# FoodTag_ADC_Schematic.net
KiCad netlist of a schematic drawn in EasyEDA
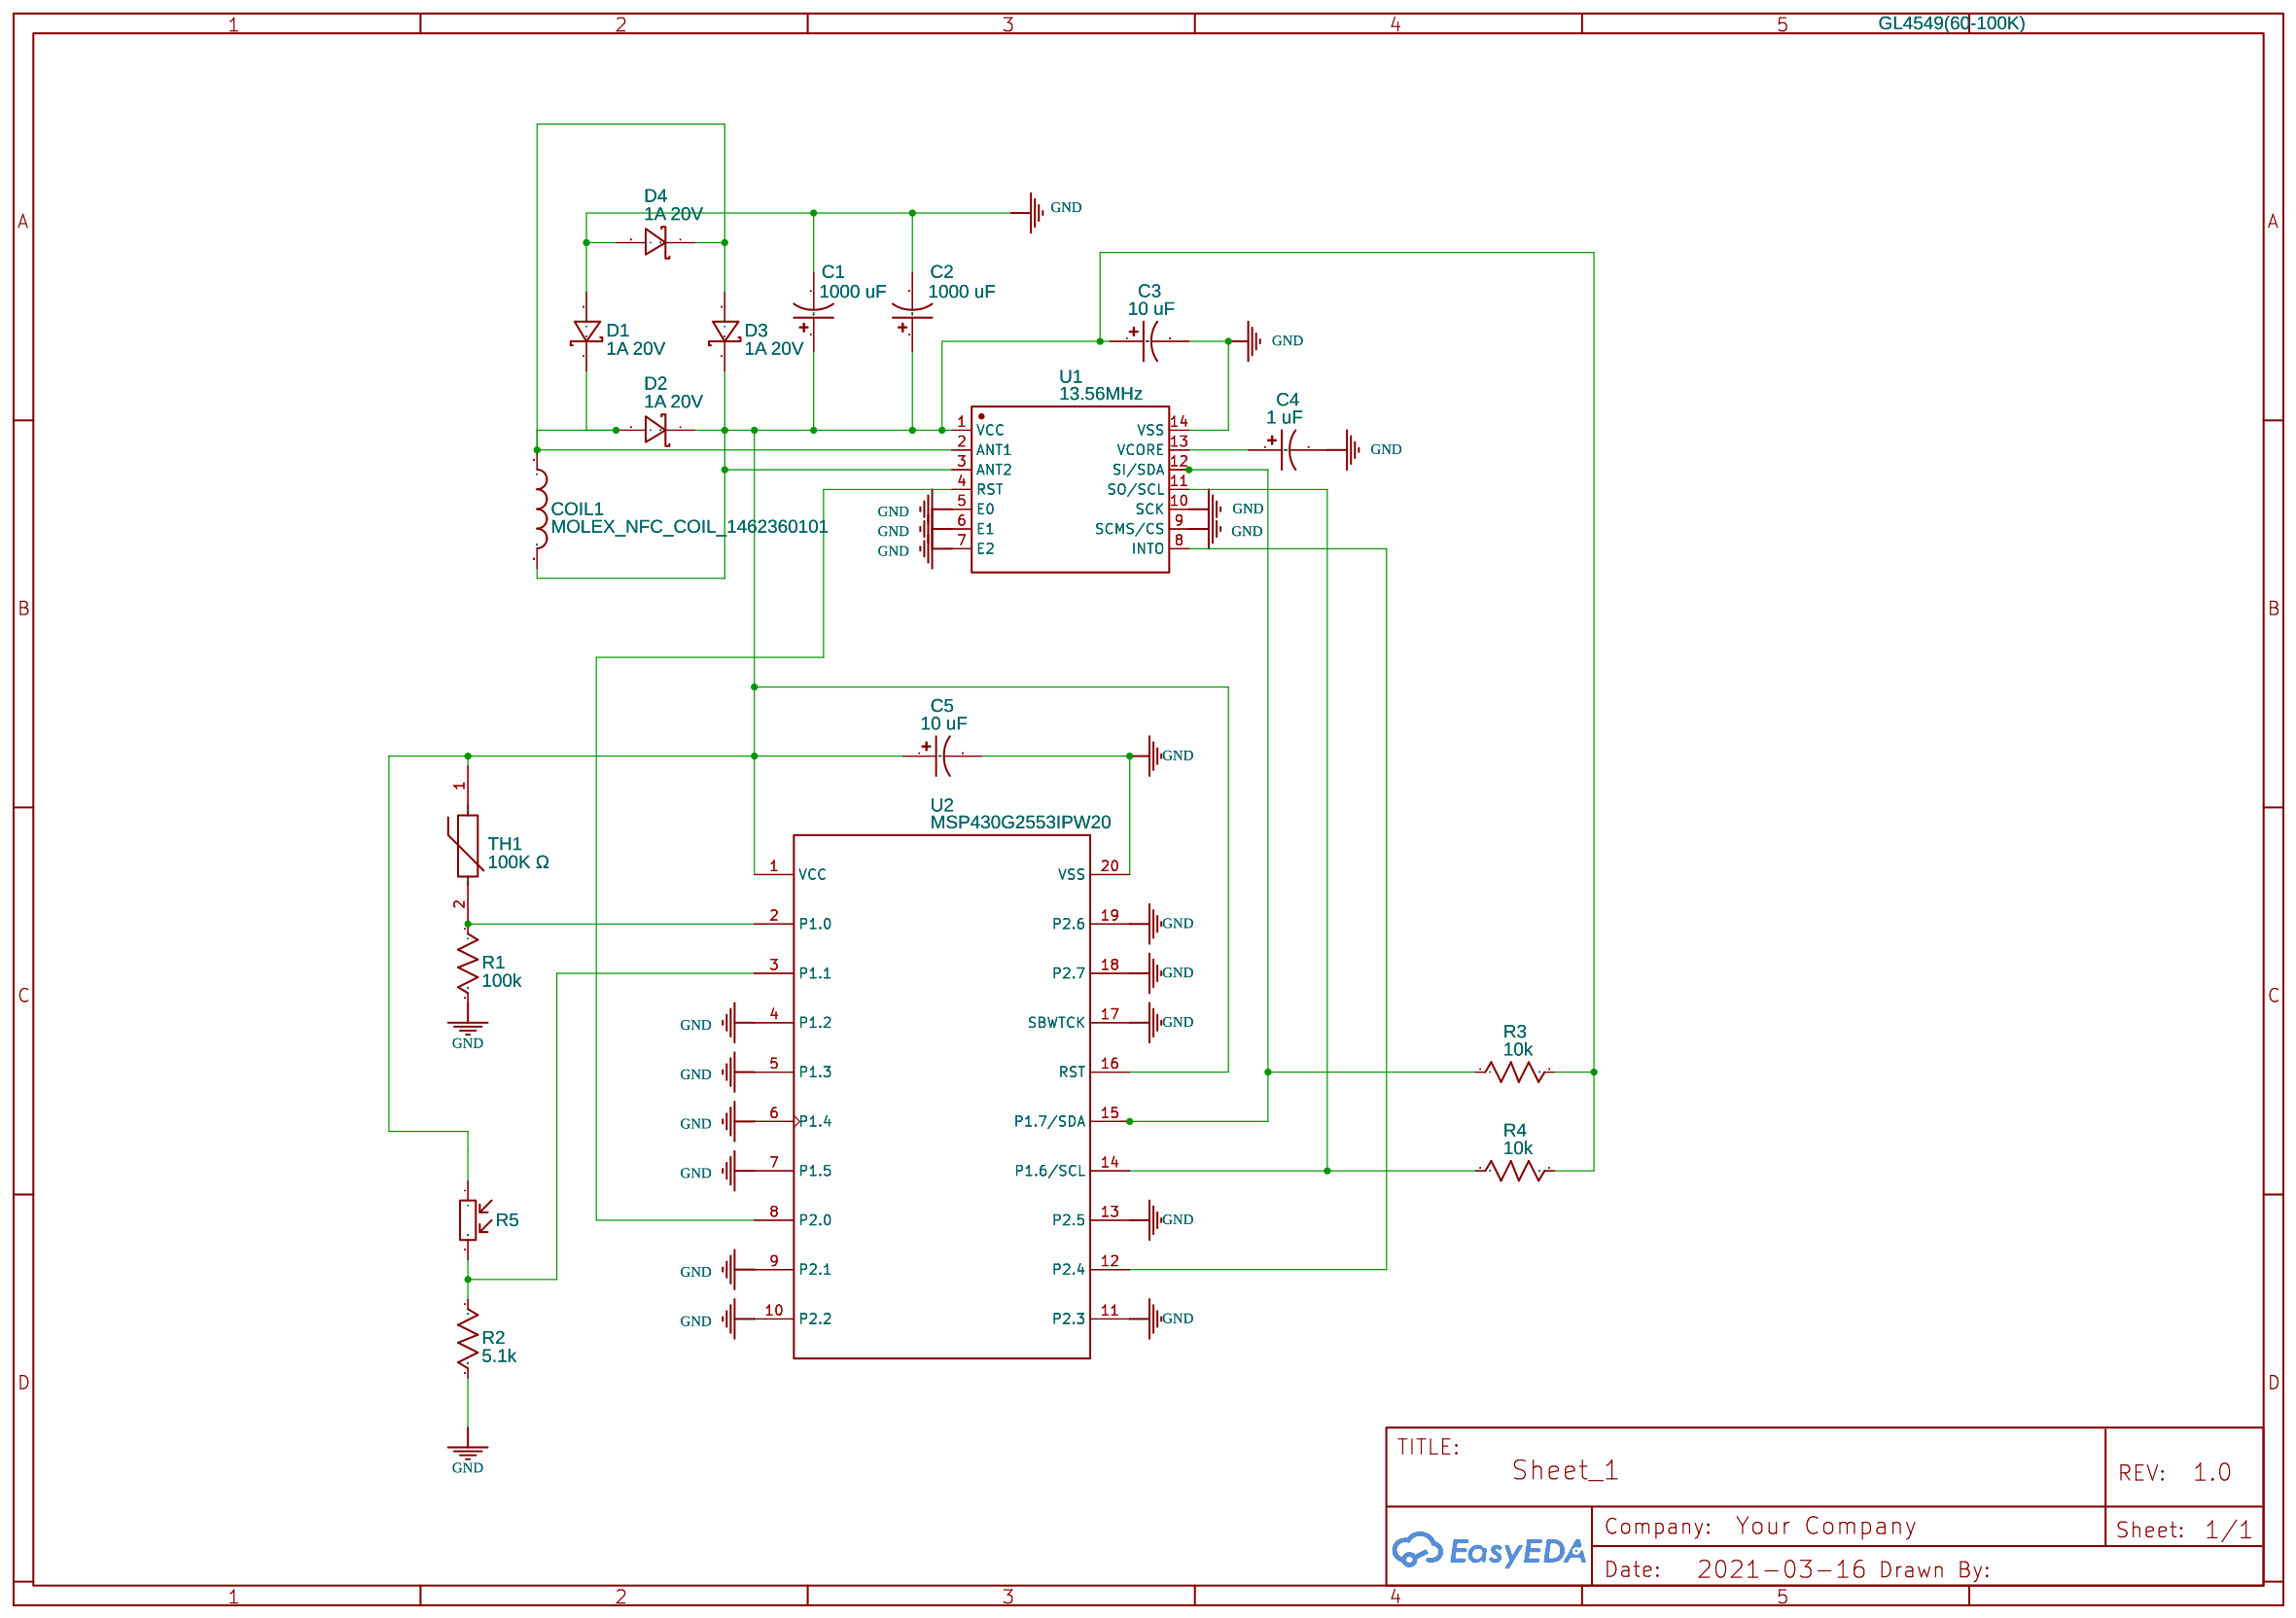
[diagram p0: schematic sheet]

(export (version "E")
  (design (tool "Eeschema 10.0.6"))
  (components
    (comp (ref "C1") (value "1000 uF") (libsource (lib "") (part "C_Tan_SMD_A_US")))
    (comp (ref "C2") (value "1000 uF") (libsource (lib "") (part "C_Tan_SMD_A_US")))
    (comp (ref "C3") (value "10 uF") (libsource (lib "") (part "C_Tan_SMD_A_US_1")))
    (comp (ref "C4") (value "1 uF") (libsource (lib "") (part "C_Tan_SMD_A_US_1")))
    (comp (ref "C5") (value "10 uF") (libsource (lib "") (part "C_Tan_SMD_A_US_1")))
    (comp (ref "COIL1")
      (value "MOLEX_NFC_COIL_1462360101")
      (libsource (lib "") (part "MOLEX_NFC_COIL_1462360101"))
    )
    (comp (ref "D1")
      (value "1A 20V")
      (fields
        (field (name "BOM_Manufacturer Part") "PMEG2010EA,115")
        (field (name "BOM_Supplier Part") "C193668")
      )
      (libsource (lib "") (part "PMEG2010EA,115_1"))
    )
    (comp (ref "D2")
      (value "1A 20V")
      (fields
        (field (name "BOM_Manufacturer Part") "PMEG2010EA,115")
        (field (name "BOM_Supplier Part") "C193668")
      )
      (libsource (lib "") (part "PMEG2010EA,115"))
    )
    (comp (ref "D3")
      (value "1A 20V")
      (fields
        (field (name "BOM_Manufacturer Part") "PMEG2010EA,115")
        (field (name "BOM_Supplier Part") "C193668")
      )
      (libsource (lib "") (part "PMEG2010EA,115_1"))
    )
    (comp (ref "D4")
      (value "1A 20V")
      (fields
        (field (name "BOM_Manufacturer Part") "PMEG2010EA,115")
        (field (name "BOM_Supplier Part") "C193668")
      )
      (libsource (lib "") (part "PMEG2010EA,115"))
    )
    (comp (ref "R1") (value "100k") (libsource (lib "") (part "R_0603_US_1")))
    (comp (ref "R2") (value "5.1k") (libsource (lib "") (part "R_0603_US_1")))
    (comp (ref "R3") (value "10k") (libsource (lib "") (part "R_0603_US")))
    (comp (ref "R4") (value "10k") (libsource (lib "") (part "R_0603_US")))
    (comp (ref "R5")
      (value "GL4549(60-100K)")
      (fields (field (name "BOM_Supplier Part") "C11297"))
      (libsource (lib "") (part "GL4549(60-100K)"))
    )
    (comp (ref "TH1")
      (value "100K Ω")
      (fields
        (field (name "BOM_Manufacturer Part") "NTCS0805E3104FXT")
        (field (name "BOM_Supplier Part") "C143680")
      )
      (libsource (lib "") (part "NTCS0805E3104FXT"))
    )
    (comp (ref "U1")
      (value "13.56MHz")
      (fields
        (field (name "BOM_Manufacturer Part") "RF430CL330HCPWR")
        (field (name "BOM_Supplier Part") "C130195")
      )
      (libsource (lib "") (part "RF430CL330HCPWR"))
    )
    (comp (ref "U2")
      (value "MSP430G2553IPW20")
      (fields (field (name "BOM_Supplier Part") "C53923"))
      (libsource (lib "") (part "MSP430G2553IPW20"))
    )
  )
  (nets
    (net (code "1") (name "GND") (class "Default")
      (node (ref "C1") (pin "2") (pinfunction "2_2") (pintype "unspecified"))
      (node (ref "C2") (pin "2") (pinfunction "2_2") (pintype "unspecified"))
      (node (ref "C3") (pin "2") (pinfunction "2_2") (pintype "unspecified"))
      (node (ref "C4") (pin "2") (pinfunction "2_2") (pintype "unspecified"))
      (node (ref "C5") (pin "2") (pinfunction "2_2") (pintype "unspecified"))
      (node (ref "D1") (pin "2") (pinfunction "A_2") (pintype "unspecified"))
      (node (ref "D4") (pin "2") (pinfunction "A_2") (pintype "unspecified"))
      (node (ref "R1") (pin "2") (pinfunction "2_2") (pintype "unspecified"))
      (node (ref "R2") (pin "2") (pinfunction "2_2") (pintype "unspecified"))
      (node (ref "U1") (pin "10") (pinfunction "SCK_10") (pintype "unspecified"))
      (node (ref "U1") (pin "14") (pinfunction "VSS_14") (pintype "unspecified"))
      (node (ref "U1") (pin "5") (pinfunction "E0_5") (pintype "unspecified"))
      (node (ref "U1") (pin "6") (pinfunction "E1_6") (pintype "unspecified"))
      (node (ref "U1") (pin "7") (pinfunction "E2_7") (pintype "unspecified"))
      (node (ref "U1") (pin "9") (pinfunction "SCMS/CS_9") (pintype "unspecified"))
      (node (ref "U2") (pin "10") (pinfunction "P2.2_10") (pintype "bidirectional"))
      (node (ref "U2") (pin "11") (pinfunction "P2.3_11") (pintype "bidirectional"))
      (node (ref "U2") (pin "13") (pinfunction "P2.5_13") (pintype "bidirectional"))
      (node (ref "U2") (pin "17") (pinfunction "SBWTCK_17") (pintype "unspecified"))
      (node (ref "U2") (pin "18") (pinfunction "P2.7_18") (pintype "bidirectional"))
      (node (ref "U2") (pin "19") (pinfunction "P2.6_19") (pintype "bidirectional"))
      (node (ref "U2") (pin "20") (pinfunction "VSS_20") (pintype "passive"))
      (node (ref "U2") (pin "4") (pinfunction "P1.2_4") (pintype "bidirectional"))
      (node (ref "U2") (pin "5") (pinfunction "P1.3_5") (pintype "bidirectional"))
      (node (ref "U2") (pin "6") (pinfunction "P1.4_6") (pintype "bidirectional"))
      (node (ref "U2") (pin "7") (pinfunction "P1.5_7") (pintype "bidirectional"))
      (node (ref "U2") (pin "9") (pinfunction "P2.1_9") (pintype "bidirectional"))
    )
    (net (code "2") (name "Net-(COIL1-1)") (class "Default")
      (node (ref "COIL1") (pin "P$1") (pinfunction "1_P$1") (pintype "bidirectional"))
      (node (ref "D1") (pin "1") (pinfunction "C_1") (pintype "unspecified"))
      (node (ref "D2") (pin "2") (pinfunction "A_2") (pintype "unspecified"))
      (node (ref "D3") (pin "2") (pinfunction "A_2") (pintype "unspecified"))
      (node (ref "D4") (pin "1") (pinfunction "C_1") (pintype "unspecified"))
      (node (ref "U1") (pin "2") (pinfunction "ANT1_2") (pintype "unspecified"))
    )
    (net (code "3") (name "Net-(COIL1-2)") (class "Default")
      (node (ref "C1") (pin "1") (pinfunction "1_1") (pintype "unspecified"))
      (node (ref "C2") (pin "1") (pinfunction "1_1") (pintype "unspecified"))
      (node (ref "C3") (pin "1") (pinfunction "1_1") (pintype "unspecified"))
      (node (ref "C5") (pin "1") (pinfunction "1_1") (pintype "unspecified"))
      (node (ref "COIL1") (pin "P$2") (pinfunction "2_P$2") (pintype "bidirectional"))
      (node (ref "D2") (pin "1") (pinfunction "C_1") (pintype "unspecified"))
      (node (ref "D3") (pin "1") (pinfunction "C_1") (pintype "unspecified"))
      (node (ref "R3") (pin "2") (pinfunction "2_2") (pintype "unspecified"))
      (node (ref "R4") (pin "2") (pinfunction "2_2") (pintype "unspecified"))
      (node (ref "R5") (pin "1") (pinfunction "1_1") (pintype "input"))
      (node (ref "TH1") (pin "1") (pinfunction "1_1") (pintype "unspecified"))
      (node (ref "U1") (pin "1") (pinfunction "VCC_1") (pintype "unspecified"))
      (node (ref "U1") (pin "3") (pinfunction "ANT2_3") (pintype "unspecified"))
      (node (ref "U2") (pin "1") (pinfunction "VCC_1") (pintype "passive"))
      (node (ref "U2") (pin "16") (pinfunction "RST_16") (pintype "bidirectional"))
    )
    (net (code "4") (name "Net-(U1-INTO)") (class "Default")
      (node (ref "U1") (pin "8") (pinfunction "INTO_8") (pintype "unspecified"))
      (node (ref "U2") (pin "12") (pinfunction "P2.4_12") (pintype "bidirectional"))
    )
    (net (code "5") (name "Net-(U1-RST)") (class "Default")
      (node (ref "U1") (pin "4") (pinfunction "RST_4") (pintype "unspecified"))
      (node (ref "U2") (pin "8") (pinfunction "P2.0_8") (pintype "bidirectional"))
    )
    (net (code "6") (name "Net-(U1-SI{slash}SDA)") (class "Default")
      (node (ref "R3") (pin "1") (pinfunction "1_1") (pintype "unspecified"))
      (node (ref "U1") (pin "12") (pinfunction "SI/SDA_12") (pintype "unspecified"))
      (node (ref "U2") (pin "15") (pinfunction "P1.7/SDA_15") (pintype "bidirectional"))
    )
    (net (code "7") (name "Net-(U1-SO{slash}SCL)") (class "Default")
      (node (ref "R4") (pin "1") (pinfunction "1_1") (pintype "unspecified"))
      (node (ref "U1") (pin "11") (pinfunction "SO/SCL_11") (pintype "unspecified"))
      (node (ref "U2") (pin "14") (pinfunction "P1.6/SCL_14") (pintype "bidirectional"))
    )
    (net (code "8") (name "Net-(U1-VCORE)") (class "Default")
      (node (ref "C4") (pin "1") (pinfunction "1_1") (pintype "unspecified"))
      (node (ref "U1") (pin "13") (pinfunction "VCORE_13") (pintype "unspecified"))
    )
    (net (code "9") (name "Net-(U2-P1.0)") (class "Default")
      (node (ref "R1") (pin "1") (pinfunction "1_1") (pintype "unspecified"))
      (node (ref "TH1") (pin "2") (pinfunction "2_2") (pintype "unspecified"))
      (node (ref "U2") (pin "2") (pinfunction "P1.0_2") (pintype "bidirectional"))
    )
    (net (code "10") (name "Net-(U2-P1.1)") (class "Default")
      (node (ref "R2") (pin "1") (pinfunction "1_1") (pintype "unspecified"))
      (node (ref "R5") (pin "2") (pinfunction "2_2") (pintype "input"))
      (node (ref "U2") (pin "3") (pinfunction "P1.1_3") (pintype "bidirectional"))
    )
  )
)
